# SoM.net
KiCad netlist of a schematic drawn in Altium Designer
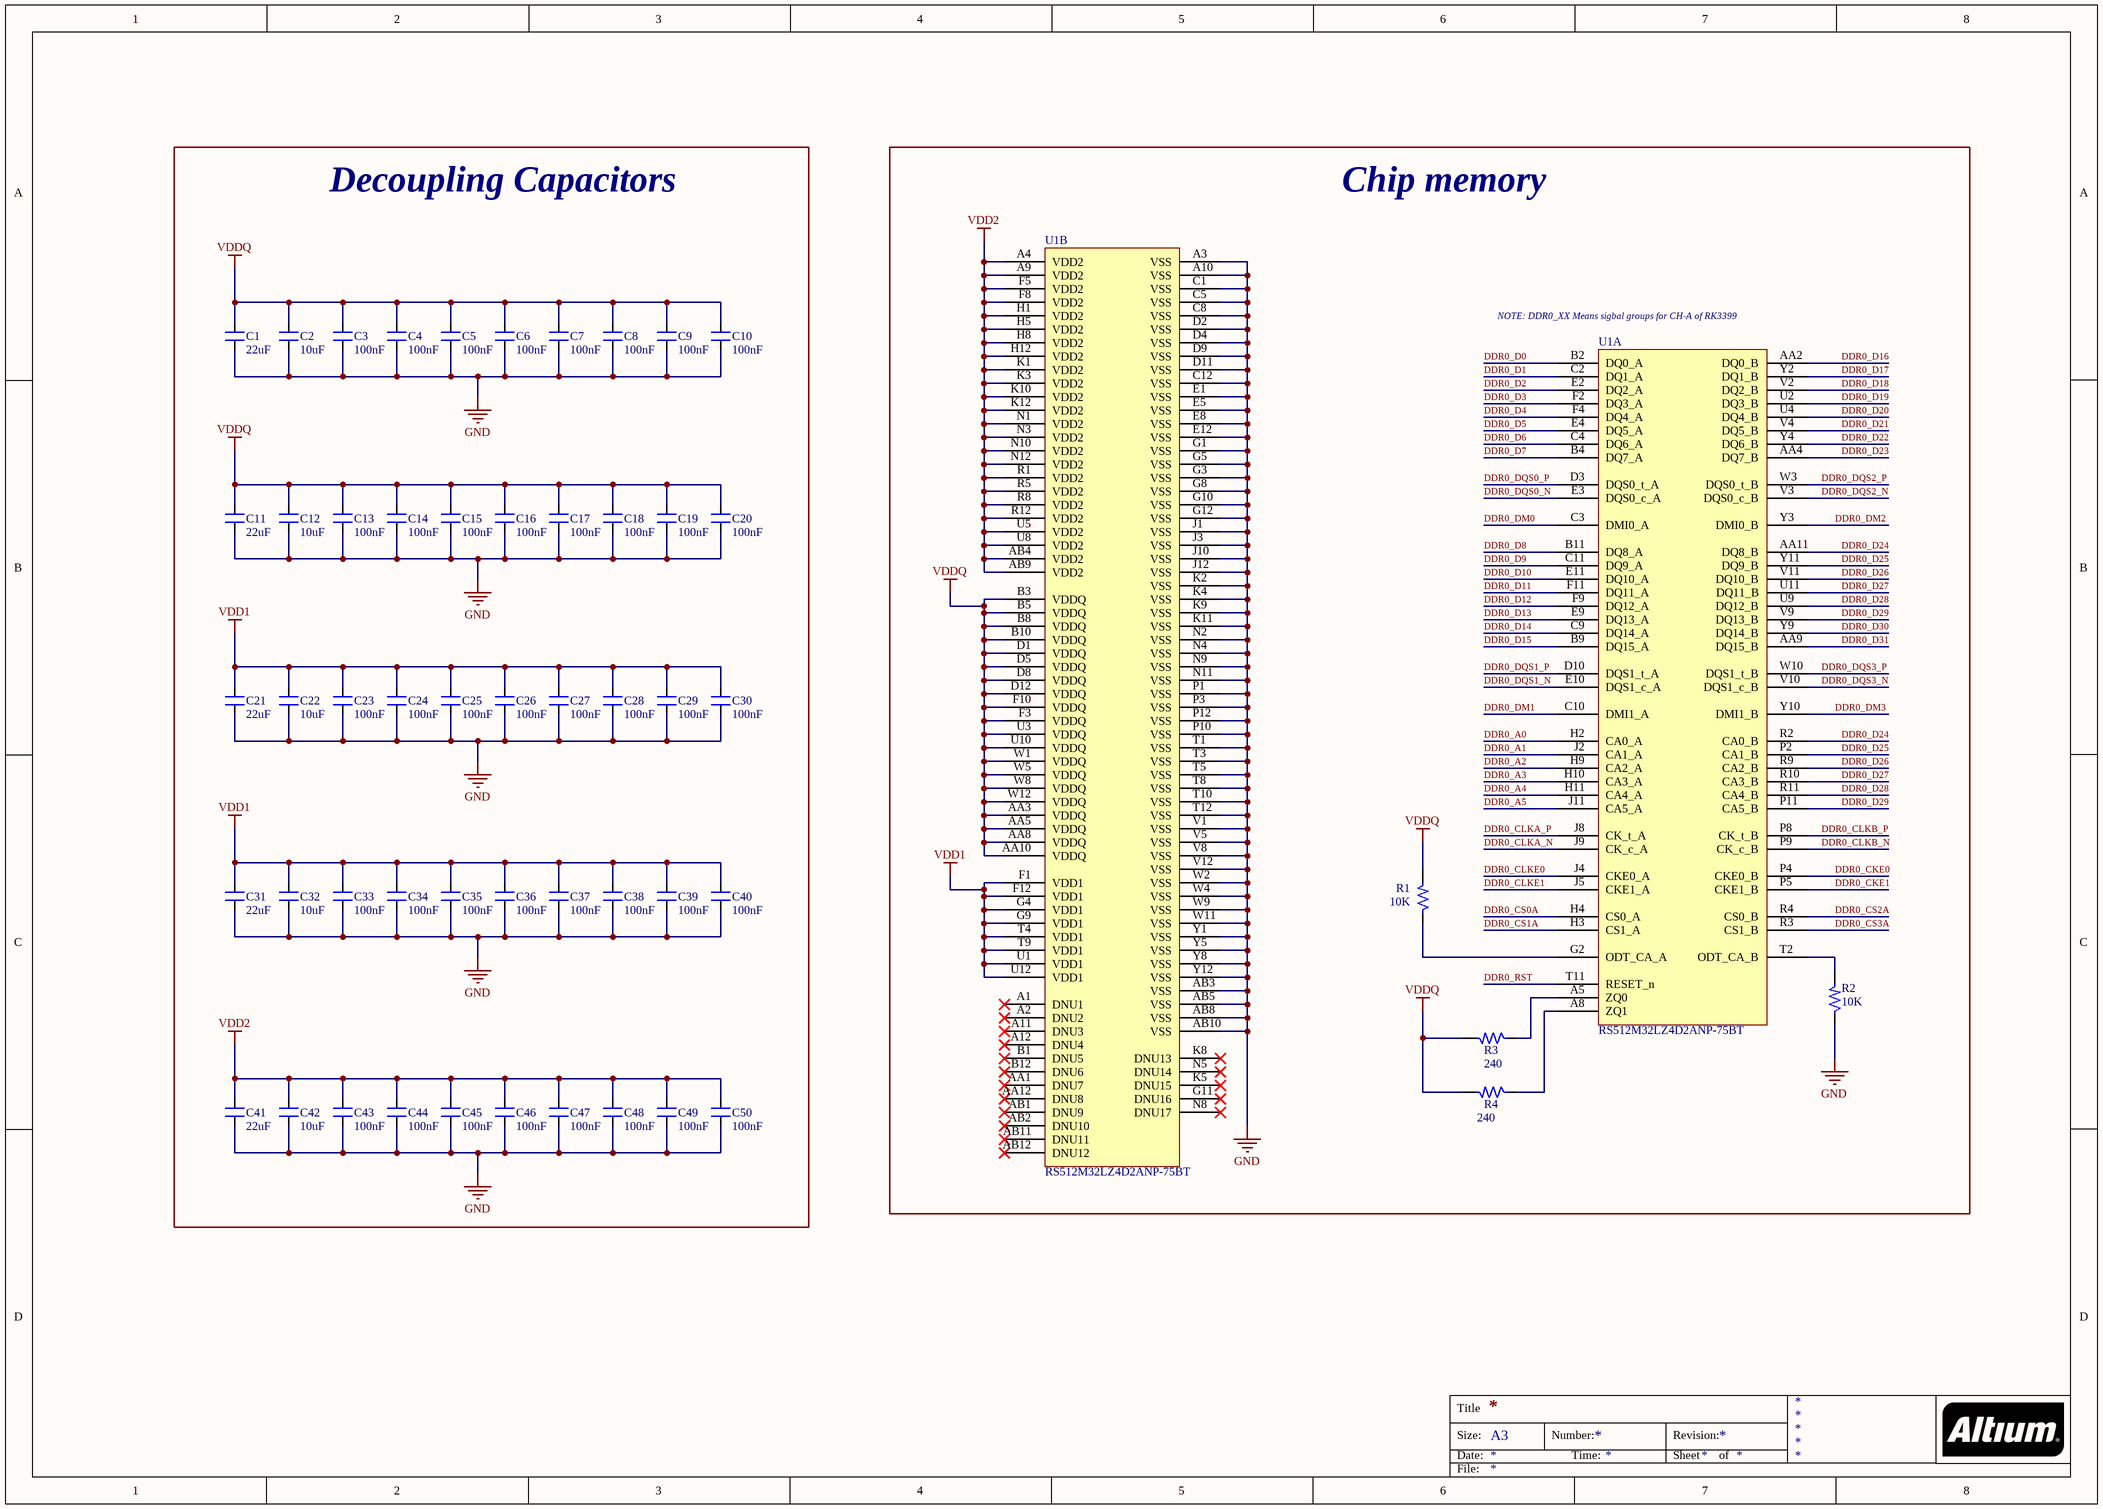
[diagram p0: SoM.SchDoc]

(export (version "E")
  (design (tool "Eeschema 10.0.6"))
  (components
    (comp (ref "C1")
      (value "22uF")
      (footprint "CAP_0603")
      (description "22µF ±20% 10V Ceramic Capacitor X5R 0603 (1608 Metric)")
      (fields
        (field (name "MANUFACTURER") "Murata Electronics")
        (field (name "MANUFACTURER PART NUMBER") "GRM188R61A226ME15D")
      )
      (libsource (lib "EsteemPCB_SOM_Course_intlib") (part "CAP_22uF-10V-20%-0603"))
    )
    (comp (ref "C2")
      (value "10uF")
      (footprint "CAP_0603")
      (description "10µF ±10% 10V Ceramic Capacitor X5R 0603 (1608 Metric)")
      (fields
        (field (name "MANUFACTURER PART NUMBER") "GRM188R61A106KE69J")
        (field (name "MANUFACTURER") "Murata Electronics")
      )
      (libsource (lib "EsteemPCB_SOM_Course_intlib") (part "CAP_10uF-10V-10%-0603"))
    )
    (comp (ref "C3")
      (value "100nF")
      (footprint "CAP_0201")
      (description "0.1µF ±10% 25V Ceramic Capacitor X5R 0201 (0603 Metric)")
      (fields
        (field (name "MANUFACTURER") "TDK Corporation")
        (field (name "MANUFACTURER PART NUMBER") "C0603X5R1E104K030BB")
      )
      (libsource (lib "EsteemPCB_SOM_Course_intlib") (part "CAP_100nF-25V-10%-0201"))
    )
    (comp (ref "C4")
      (value "100nF")
      (footprint "CAP_0201")
      (description "0.1µF ±10% 25V Ceramic Capacitor X5R 0201 (0603 Metric)")
      (fields
        (field (name "MANUFACTURER") "TDK Corporation")
        (field (name "MANUFACTURER PART NUMBER") "C0603X5R1E104K030BB")
      )
      (libsource (lib "EsteemPCB_SOM_Course_intlib") (part "CAP_100nF-25V-10%-0201"))
    )
    (comp (ref "C5")
      (value "100nF")
      (footprint "CAP_0201")
      (description "0.1µF ±10% 25V Ceramic Capacitor X5R 0201 (0603 Metric)")
      (fields
        (field (name "MANUFACTURER") "TDK Corporation")
        (field (name "MANUFACTURER PART NUMBER") "C0603X5R1E104K030BB")
      )
      (libsource (lib "EsteemPCB_SOM_Course_intlib") (part "CAP_100nF-25V-10%-0201"))
    )
    (comp (ref "C6")
      (value "100nF")
      (footprint "CAP_0201")
      (description "0.1µF ±10% 25V Ceramic Capacitor X5R 0201 (0603 Metric)")
      (fields
        (field (name "MANUFACTURER") "TDK Corporation")
        (field (name "MANUFACTURER PART NUMBER") "C0603X5R1E104K030BB")
      )
      (libsource (lib "EsteemPCB_SOM_Course_intlib") (part "CAP_100nF-25V-10%-0201"))
    )
    (comp (ref "C7")
      (value "100nF")
      (footprint "CAP_0201")
      (description "0.1µF ±10% 25V Ceramic Capacitor X5R 0201 (0603 Metric)")
      (fields
        (field (name "MANUFACTURER") "TDK Corporation")
        (field (name "MANUFACTURER PART NUMBER") "C0603X5R1E104K030BB")
      )
      (libsource (lib "EsteemPCB_SOM_Course_intlib") (part "CAP_100nF-25V-10%-0201"))
    )
    (comp (ref "C8")
      (value "100nF")
      (footprint "CAP_0201")
      (description "0.1µF ±10% 25V Ceramic Capacitor X5R 0201 (0603 Metric)")
      (fields
        (field (name "MANUFACTURER") "TDK Corporation")
        (field (name "MANUFACTURER PART NUMBER") "C0603X5R1E104K030BB")
      )
      (libsource (lib "EsteemPCB_SOM_Course_intlib") (part "CAP_100nF-25V-10%-0201"))
    )
    (comp (ref "C9")
      (value "100nF")
      (footprint "CAP_0201")
      (description "0.1µF ±10% 25V Ceramic Capacitor X5R 0201 (0603 Metric)")
      (fields
        (field (name "MANUFACTURER") "TDK Corporation")
        (field (name "MANUFACTURER PART NUMBER") "C0603X5R1E104K030BB")
      )
      (libsource (lib "EsteemPCB_SOM_Course_intlib") (part "CAP_100nF-25V-10%-0201"))
    )
    (comp (ref "C10")
      (value "100nF")
      (footprint "CAP_0201")
      (description "0.1µF ±10% 25V Ceramic Capacitor X5R 0201 (0603 Metric)")
      (fields
        (field (name "MANUFACTURER") "TDK Corporation")
        (field (name "MANUFACTURER PART NUMBER") "C0603X5R1E104K030BB")
      )
      (libsource (lib "EsteemPCB_SOM_Course_intlib") (part "CAP_100nF-25V-10%-0201"))
    )
    (comp (ref "C11")
      (value "22uF")
      (footprint "CAP_0603")
      (description "22µF ±20% 10V Ceramic Capacitor X5R 0603 (1608 Metric)")
      (fields
        (field (name "MANUFACTURER") "Murata Electronics")
        (field (name "MANUFACTURER PART NUMBER") "GRM188R61A226ME15D")
      )
      (libsource (lib "EsteemPCB_SOM_Course_intlib") (part "CAP_22uF-10V-20%-0603"))
    )
    (comp (ref "C12")
      (value "10uF")
      (footprint "CAP_0603")
      (description "10µF ±10% 10V Ceramic Capacitor X5R 0603 (1608 Metric)")
      (fields
        (field (name "MANUFACTURER PART NUMBER") "GRM188R61A106KE69J")
        (field (name "MANUFACTURER") "Murata Electronics")
      )
      (libsource (lib "EsteemPCB_SOM_Course_intlib") (part "CAP_10uF-10V-10%-0603"))
    )
    (comp (ref "C13")
      (value "100nF")
      (footprint "CAP_0201")
      (description "0.1µF ±10% 25V Ceramic Capacitor X5R 0201 (0603 Metric)")
      (fields
        (field (name "MANUFACTURER") "TDK Corporation")
        (field (name "MANUFACTURER PART NUMBER") "C0603X5R1E104K030BB")
      )
      (libsource (lib "EsteemPCB_SOM_Course_intlib") (part "CAP_100nF-25V-10%-0201"))
    )
    (comp (ref "C14")
      (value "100nF")
      (footprint "CAP_0201")
      (description "0.1µF ±10% 25V Ceramic Capacitor X5R 0201 (0603 Metric)")
      (fields
        (field (name "MANUFACTURER") "TDK Corporation")
        (field (name "MANUFACTURER PART NUMBER") "C0603X5R1E104K030BB")
      )
      (libsource (lib "EsteemPCB_SOM_Course_intlib") (part "CAP_100nF-25V-10%-0201"))
    )
    (comp (ref "C15")
      (value "100nF")
      (footprint "CAP_0201")
      (description "0.1µF ±10% 25V Ceramic Capacitor X5R 0201 (0603 Metric)")
      (fields
        (field (name "MANUFACTURER") "TDK Corporation")
        (field (name "MANUFACTURER PART NUMBER") "C0603X5R1E104K030BB")
      )
      (libsource (lib "EsteemPCB_SOM_Course_intlib") (part "CAP_100nF-25V-10%-0201"))
    )
    (comp (ref "C16")
      (value "100nF")
      (footprint "CAP_0201")
      (description "0.1µF ±10% 25V Ceramic Capacitor X5R 0201 (0603 Metric)")
      (fields
        (field (name "MANUFACTURER") "TDK Corporation")
        (field (name "MANUFACTURER PART NUMBER") "C0603X5R1E104K030BB")
      )
      (libsource (lib "EsteemPCB_SOM_Course_intlib") (part "CAP_100nF-25V-10%-0201"))
    )
    (comp (ref "C17")
      (value "100nF")
      (footprint "CAP_0201")
      (description "0.1µF ±10% 25V Ceramic Capacitor X5R 0201 (0603 Metric)")
      (fields
        (field (name "MANUFACTURER") "TDK Corporation")
        (field (name "MANUFACTURER PART NUMBER") "C0603X5R1E104K030BB")
      )
      (libsource (lib "EsteemPCB_SOM_Course_intlib") (part "CAP_100nF-25V-10%-0201"))
    )
    (comp (ref "C18")
      (value "100nF")
      (footprint "CAP_0201")
      (description "0.1µF ±10% 25V Ceramic Capacitor X5R 0201 (0603 Metric)")
      (fields
        (field (name "MANUFACTURER") "TDK Corporation")
        (field (name "MANUFACTURER PART NUMBER") "C0603X5R1E104K030BB")
      )
      (libsource (lib "EsteemPCB_SOM_Course_intlib") (part "CAP_100nF-25V-10%-0201"))
    )
    (comp (ref "C19")
      (value "100nF")
      (footprint "CAP_0201")
      (description "0.1µF ±10% 25V Ceramic Capacitor X5R 0201 (0603 Metric)")
      (fields
        (field (name "MANUFACTURER") "TDK Corporation")
        (field (name "MANUFACTURER PART NUMBER") "C0603X5R1E104K030BB")
      )
      (libsource (lib "EsteemPCB_SOM_Course_intlib") (part "CAP_100nF-25V-10%-0201"))
    )
    (comp (ref "C20")
      (value "100nF")
      (footprint "CAP_0201")
      (description "0.1µF ±10% 25V Ceramic Capacitor X5R 0201 (0603 Metric)")
      (fields
        (field (name "MANUFACTURER") "TDK Corporation")
        (field (name "MANUFACTURER PART NUMBER") "C0603X5R1E104K030BB")
      )
      (libsource (lib "EsteemPCB_SOM_Course_intlib") (part "CAP_100nF-25V-10%-0201"))
    )
    (comp (ref "C21")
      (value "22uF")
      (footprint "CAP_0603")
      (description "22µF ±20% 10V Ceramic Capacitor X5R 0603 (1608 Metric)")
      (fields
        (field (name "MANUFACTURER") "Murata Electronics")
        (field (name "MANUFACTURER PART NUMBER") "GRM188R61A226ME15D")
      )
      (libsource (lib "EsteemPCB_SOM_Course_intlib") (part "CAP_22uF-10V-20%-0603"))
    )
    (comp (ref "C22")
      (value "10uF")
      (footprint "CAP_0603")
      (description "10µF ±10% 10V Ceramic Capacitor X5R 0603 (1608 Metric)")
      (fields
        (field (name "MANUFACTURER PART NUMBER") "GRM188R61A106KE69J")
        (field (name "MANUFACTURER") "Murata Electronics")
      )
      (libsource (lib "EsteemPCB_SOM_Course_intlib") (part "CAP_10uF-10V-10%-0603"))
    )
    (comp (ref "C23")
      (value "100nF")
      (footprint "CAP_0201")
      (description "0.1µF ±10% 25V Ceramic Capacitor X5R 0201 (0603 Metric)")
      (fields
        (field (name "MANUFACTURER") "TDK Corporation")
        (field (name "MANUFACTURER PART NUMBER") "C0603X5R1E104K030BB")
      )
      (libsource (lib "EsteemPCB_SOM_Course_intlib") (part "CAP_100nF-25V-10%-0201"))
    )
    (comp (ref "C24")
      (value "100nF")
      (footprint "CAP_0201")
      (description "0.1µF ±10% 25V Ceramic Capacitor X5R 0201 (0603 Metric)")
      (fields
        (field (name "MANUFACTURER") "TDK Corporation")
        (field (name "MANUFACTURER PART NUMBER") "C0603X5R1E104K030BB")
      )
      (libsource (lib "EsteemPCB_SOM_Course_intlib") (part "CAP_100nF-25V-10%-0201"))
    )
    (comp (ref "C25")
      (value "100nF")
      (footprint "CAP_0201")
      (description "0.1µF ±10% 25V Ceramic Capacitor X5R 0201 (0603 Metric)")
      (fields
        (field (name "MANUFACTURER") "TDK Corporation")
        (field (name "MANUFACTURER PART NUMBER") "C0603X5R1E104K030BB")
      )
      (libsource (lib "EsteemPCB_SOM_Course_intlib") (part "CAP_100nF-25V-10%-0201"))
    )
    (comp (ref "C26")
      (value "100nF")
      (footprint "CAP_0201")
      (description "0.1µF ±10% 25V Ceramic Capacitor X5R 0201 (0603 Metric)")
      (fields
        (field (name "MANUFACTURER") "TDK Corporation")
        (field (name "MANUFACTURER PART NUMBER") "C0603X5R1E104K030BB")
      )
      (libsource (lib "EsteemPCB_SOM_Course_intlib") (part "CAP_100nF-25V-10%-0201"))
    )
    (comp (ref "C27")
      (value "100nF")
      (footprint "CAP_0201")
      (description "0.1µF ±10% 25V Ceramic Capacitor X5R 0201 (0603 Metric)")
      (fields
        (field (name "MANUFACTURER") "TDK Corporation")
        (field (name "MANUFACTURER PART NUMBER") "C0603X5R1E104K030BB")
      )
      (libsource (lib "EsteemPCB_SOM_Course_intlib") (part "CAP_100nF-25V-10%-0201"))
    )
    (comp (ref "C28")
      (value "100nF")
      (footprint "CAP_0201")
      (description "0.1µF ±10% 25V Ceramic Capacitor X5R 0201 (0603 Metric)")
      (fields
        (field (name "MANUFACTURER") "TDK Corporation")
        (field (name "MANUFACTURER PART NUMBER") "C0603X5R1E104K030BB")
      )
      (libsource (lib "EsteemPCB_SOM_Course_intlib") (part "CAP_100nF-25V-10%-0201"))
    )
    (comp (ref "C29")
      (value "100nF")
      (footprint "CAP_0201")
      (description "0.1µF ±10% 25V Ceramic Capacitor X5R 0201 (0603 Metric)")
      (fields
        (field (name "MANUFACTURER") "TDK Corporation")
        (field (name "MANUFACTURER PART NUMBER") "C0603X5R1E104K030BB")
      )
      (libsource (lib "EsteemPCB_SOM_Course_intlib") (part "CAP_100nF-25V-10%-0201"))
    )
    (comp (ref "C30")
      (value "100nF")
      (footprint "CAP_0201")
      (description "0.1µF ±10% 25V Ceramic Capacitor X5R 0201 (0603 Metric)")
      (fields
        (field (name "MANUFACTURER") "TDK Corporation")
        (field (name "MANUFACTURER PART NUMBER") "C0603X5R1E104K030BB")
      )
      (libsource (lib "EsteemPCB_SOM_Course_intlib") (part "CAP_100nF-25V-10%-0201"))
    )
    (comp (ref "C31")
      (value "22uF")
      (footprint "CAP_0603")
      (description "22µF ±20% 10V Ceramic Capacitor X5R 0603 (1608 Metric)")
      (fields
        (field (name "MANUFACTURER") "Murata Electronics")
        (field (name "MANUFACTURER PART NUMBER") "GRM188R61A226ME15D")
      )
      (libsource (lib "EsteemPCB_SOM_Course_intlib") (part "CAP_22uF-10V-20%-0603"))
    )
    (comp (ref "C32")
      (value "10uF")
      (footprint "CAP_0603")
      (description "10µF ±10% 10V Ceramic Capacitor X5R 0603 (1608 Metric)")
      (fields
        (field (name "MANUFACTURER PART NUMBER") "GRM188R61A106KE69J")
        (field (name "MANUFACTURER") "Murata Electronics")
      )
      (libsource (lib "EsteemPCB_SOM_Course_intlib") (part "CAP_10uF-10V-10%-0603"))
    )
    (comp (ref "C33")
      (value "100nF")
      (footprint "CAP_0201")
      (description "0.1µF ±10% 25V Ceramic Capacitor X5R 0201 (0603 Metric)")
      (fields
        (field (name "MANUFACTURER") "TDK Corporation")
        (field (name "MANUFACTURER PART NUMBER") "C0603X5R1E104K030BB")
      )
      (libsource (lib "EsteemPCB_SOM_Course_intlib") (part "CAP_100nF-25V-10%-0201"))
    )
    (comp (ref "C34")
      (value "100nF")
      (footprint "CAP_0201")
      (description "0.1µF ±10% 25V Ceramic Capacitor X5R 0201 (0603 Metric)")
      (fields
        (field (name "MANUFACTURER") "TDK Corporation")
        (field (name "MANUFACTURER PART NUMBER") "C0603X5R1E104K030BB")
      )
      (libsource (lib "EsteemPCB_SOM_Course_intlib") (part "CAP_100nF-25V-10%-0201"))
    )
    (comp (ref "C35")
      (value "100nF")
      (footprint "CAP_0201")
      (description "0.1µF ±10% 25V Ceramic Capacitor X5R 0201 (0603 Metric)")
      (fields
        (field (name "MANUFACTURER") "TDK Corporation")
        (field (name "MANUFACTURER PART NUMBER") "C0603X5R1E104K030BB")
      )
      (libsource (lib "EsteemPCB_SOM_Course_intlib") (part "CAP_100nF-25V-10%-0201"))
    )
    (comp (ref "C36")
      (value "100nF")
      (footprint "CAP_0201")
      (description "0.1µF ±10% 25V Ceramic Capacitor X5R 0201 (0603 Metric)")
      (fields
        (field (name "MANUFACTURER") "TDK Corporation")
        (field (name "MANUFACTURER PART NUMBER") "C0603X5R1E104K030BB")
      )
      (libsource (lib "EsteemPCB_SOM_Course_intlib") (part "CAP_100nF-25V-10%-0201"))
    )
    (comp (ref "C37")
      (value "100nF")
      (footprint "CAP_0201")
      (description "0.1µF ±10% 25V Ceramic Capacitor X5R 0201 (0603 Metric)")
      (fields
        (field (name "MANUFACTURER") "TDK Corporation")
        (field (name "MANUFACTURER PART NUMBER") "C0603X5R1E104K030BB")
      )
      (libsource (lib "EsteemPCB_SOM_Course_intlib") (part "CAP_100nF-25V-10%-0201"))
    )
    (comp (ref "C38")
      (value "100nF")
      (footprint "CAP_0201")
      (description "0.1µF ±10% 25V Ceramic Capacitor X5R 0201 (0603 Metric)")
      (fields
        (field (name "MANUFACTURER") "TDK Corporation")
        (field (name "MANUFACTURER PART NUMBER") "C0603X5R1E104K030BB")
      )
      (libsource (lib "EsteemPCB_SOM_Course_intlib") (part "CAP_100nF-25V-10%-0201"))
    )
    (comp (ref "C39")
      (value "100nF")
      (footprint "CAP_0201")
      (description "0.1µF ±10% 25V Ceramic Capacitor X5R 0201 (0603 Metric)")
      (fields
        (field (name "MANUFACTURER") "TDK Corporation")
        (field (name "MANUFACTURER PART NUMBER") "C0603X5R1E104K030BB")
      )
      (libsource (lib "EsteemPCB_SOM_Course_intlib") (part "CAP_100nF-25V-10%-0201"))
    )
    (comp (ref "C40")
      (value "100nF")
      (footprint "CAP_0201")
      (description "0.1µF ±10% 25V Ceramic Capacitor X5R 0201 (0603 Metric)")
      (fields
        (field (name "MANUFACTURER") "TDK Corporation")
        (field (name "MANUFACTURER PART NUMBER") "C0603X5R1E104K030BB")
      )
      (libsource (lib "EsteemPCB_SOM_Course_intlib") (part "CAP_100nF-25V-10%-0201"))
    )
    (comp (ref "C41")
      (value "22uF")
      (footprint "CAP_0603")
      (description "22µF ±20% 10V Ceramic Capacitor X5R 0603 (1608 Metric)")
      (fields
        (field (name "MANUFACTURER") "Murata Electronics")
        (field (name "MANUFACTURER PART NUMBER") "GRM188R61A226ME15D")
      )
      (libsource (lib "EsteemPCB_SOM_Course_intlib") (part "CAP_22uF-10V-20%-0603"))
    )
    (comp (ref "C42")
      (value "10uF")
      (footprint "CAP_0603")
      (description "10µF ±10% 10V Ceramic Capacitor X5R 0603 (1608 Metric)")
      (fields
        (field (name "MANUFACTURER PART NUMBER") "GRM188R61A106KE69J")
        (field (name "MANUFACTURER") "Murata Electronics")
      )
      (libsource (lib "EsteemPCB_SOM_Course_intlib") (part "CAP_10uF-10V-10%-0603"))
    )
    (comp (ref "C43")
      (value "100nF")
      (footprint "CAP_0201")
      (description "0.1µF ±10% 25V Ceramic Capacitor X5R 0201 (0603 Metric)")
      (fields
        (field (name "MANUFACTURER") "TDK Corporation")
        (field (name "MANUFACTURER PART NUMBER") "C0603X5R1E104K030BB")
      )
      (libsource (lib "EsteemPCB_SOM_Course_intlib") (part "CAP_100nF-25V-10%-0201"))
    )
    (comp (ref "C44")
      (value "100nF")
      (footprint "CAP_0201")
      (description "0.1µF ±10% 25V Ceramic Capacitor X5R 0201 (0603 Metric)")
      (fields
        (field (name "MANUFACTURER") "TDK Corporation")
        (field (name "MANUFACTURER PART NUMBER") "C0603X5R1E104K030BB")
      )
      (libsource (lib "EsteemPCB_SOM_Course_intlib") (part "CAP_100nF-25V-10%-0201"))
    )
    (comp (ref "C45")
      (value "100nF")
      (footprint "CAP_0201")
      (description "0.1µF ±10% 25V Ceramic Capacitor X5R 0201 (0603 Metric)")
      (fields
        (field (name "MANUFACTURER") "TDK Corporation")
        (field (name "MANUFACTURER PART NUMBER") "C0603X5R1E104K030BB")
      )
      (libsource (lib "EsteemPCB_SOM_Course_intlib") (part "CAP_100nF-25V-10%-0201"))
    )
    (comp (ref "C46")
      (value "100nF")
      (footprint "CAP_0201")
      (description "0.1µF ±10% 25V Ceramic Capacitor X5R 0201 (0603 Metric)")
      (fields
        (field (name "MANUFACTURER") "TDK Corporation")
        (field (name "MANUFACTURER PART NUMBER") "C0603X5R1E104K030BB")
      )
      (libsource (lib "EsteemPCB_SOM_Course_intlib") (part "CAP_100nF-25V-10%-0201"))
    )
    (comp (ref "C47")
      (value "100nF")
      (footprint "CAP_0201")
      (description "0.1µF ±10% 25V Ceramic Capacitor X5R 0201 (0603 Metric)")
      (fields
        (field (name "MANUFACTURER") "TDK Corporation")
        (field (name "MANUFACTURER PART NUMBER") "C0603X5R1E104K030BB")
      )
      (libsource (lib "EsteemPCB_SOM_Course_intlib") (part "CAP_100nF-25V-10%-0201"))
    )
    (comp (ref "C48")
      (value "100nF")
      (footprint "CAP_0201")
      (description "0.1µF ±10% 25V Ceramic Capacitor X5R 0201 (0603 Metric)")
      (fields
        (field (name "MANUFACTURER") "TDK Corporation")
        (field (name "MANUFACTURER PART NUMBER") "C0603X5R1E104K030BB")
      )
      (libsource (lib "EsteemPCB_SOM_Course_intlib") (part "CAP_100nF-25V-10%-0201"))
    )
    (comp (ref "C49")
      (value "100nF")
      (footprint "CAP_0201")
      (description "0.1µF ±10% 25V Ceramic Capacitor X5R 0201 (0603 Metric)")
      (fields
        (field (name "MANUFACTURER") "TDK Corporation")
        (field (name "MANUFACTURER PART NUMBER") "C0603X5R1E104K030BB")
      )
      (libsource (lib "EsteemPCB_SOM_Course_intlib") (part "CAP_100nF-25V-10%-0201"))
    )
    (comp (ref "C50")
      (value "100nF")
      (footprint "CAP_0201")
      (description "0.1µF ±10% 25V Ceramic Capacitor X5R 0201 (0603 Metric)")
      (fields
        (field (name "MANUFACTURER") "TDK Corporation")
        (field (name "MANUFACTURER PART NUMBER") "C0603X5R1E104K030BB")
      )
      (libsource (lib "EsteemPCB_SOM_Course_intlib") (part "CAP_100nF-25V-10%-0201"))
    )
    (comp (ref "R1")
      (value "10K")
      (footprint "RES_0201")
      (description "10 kOhms ±1% 0.05W, 1/20W Chip Resistor 0201 (0603 Metric) Thick Film")
      (fields
        (field (name "MANUFACTURER") "Stackpole Electronics Inc")
        (field (name "MANUFACTURER PART NUMBER") "RMCF0201FT10K0")
      )
      (libsource (lib "EsteemPCB_SOM_Course_intlib") (part "RES_10K-0.05W-1%-0201"))
    )
    (comp (ref "R2")
      (value "10K")
      (footprint "RES_0201")
      (description "10 kOhms ±1% 0.05W, 1/20W Chip Resistor 0201 (0603 Metric) Thick Film")
      (fields
        (field (name "MANUFACTURER") "Stackpole Electronics Inc")
        (field (name "MANUFACTURER PART NUMBER") "RMCF0201FT10K0")
      )
      (libsource (lib "EsteemPCB_SOM_Course_intlib") (part "RES_10K-0.05W-1%-0201"))
    )
    (comp (ref "R3")
      (value "240")
      (footprint "RES_0201")
      (description "10 kOhms ±1% 0.05W, 1/20W Chip Resistor 0201 (0603 Metric) Thick Film")
      (fields
        (field (name "MANUFACTURER") "Stackpole Electronics Inc")
        (field (name "MANUFACTURER PART NUMBER") "RMCF0201FT10K0")
      )
      (libsource (lib "EsteemPCB_SOM_Course_intlib") (part "RES_10K-0.05W-1%-0201"))
    )
    (comp (ref "R4")
      (value "240")
      (footprint "RES_0201")
      (description "10 kOhms ±1% 0.05W, 1/20W Chip Resistor 0201 (0603 Metric) Thick Film")
      (fields
        (field (name "MANUFACTURER") "Stackpole Electronics Inc")
        (field (name "MANUFACTURER PART NUMBER") "RMCF0201FT10K0")
      )
      (libsource (lib "EsteemPCB_SOM_Course_intlib") (part "RES_10K-0.05W-1%-0201"))
    )
    (comp (ref "U1")
      (value "RS512M32LZ4D2ANP-75BT")
      (footprint "FBGA200_SMD")
      (fields (field (name "MANUFACTURER") "RAYSON"))
      (libsource (lib "EsteemPCB_SOM_Course_intlib") (part "IC_RS512M32LZ4D2ANP-75BT"))
    )
  )
  (nets
    (net (code "1") (name "/DDR0_A0") (class "Default")
      (node (ref "U1") (pin "H2") (pinfunction "CA0_A_H2") (pintype "passive"))
    )
    (net (code "2") (name "/DDR0_A1") (class "Default")
      (node (ref "U1") (pin "J2") (pinfunction "CA1_A_J2") (pintype "passive"))
    )
    (net (code "3") (name "/DDR0_A2") (class "Default")
      (node (ref "U1") (pin "H9") (pinfunction "CA2_A_H9") (pintype "passive"))
    )
    (net (code "4") (name "/DDR0_A3") (class "Default")
      (node (ref "U1") (pin "H10") (pinfunction "CA3_A_H10") (pintype "passive"))
    )
    (net (code "5") (name "/DDR0_A4") (class "Default")
      (node (ref "U1") (pin "H11") (pinfunction "CA4_A_H11") (pintype "passive"))
    )
    (net (code "6") (name "/DDR0_A5") (class "Default")
      (node (ref "U1") (pin "J11") (pinfunction "CA5_A_J11") (pintype "passive"))
    )
    (net (code "7") (name "/DDR0_CKE0") (class "Default")
      (node (ref "U1") (pin "P4") (pinfunction "CKE0_B_P4") (pintype "passive"))
    )
    (net (code "8") (name "/DDR0_CKE1") (class "Default")
      (node (ref "U1") (pin "P5") (pinfunction "CKE1_B_P5") (pintype "passive"))
    )
    (net (code "9") (name "/DDR0_CLKA_N") (class "Default")
      (node (ref "U1") (pin "J9") (pinfunction "CK_c_A_J9") (pintype "passive"))
    )
    (net (code "10") (name "/DDR0_CLKA_P") (class "Default")
      (node (ref "U1") (pin "J8") (pinfunction "CK_t_A_J8") (pintype "passive"))
    )
    (net (code "11") (name "/DDR0_CLKB_N") (class "Default")
      (node (ref "U1") (pin "P9") (pinfunction "CK_c_B_P9") (pintype "passive"))
    )
    (net (code "12") (name "/DDR0_CLKB_P") (class "Default")
      (node (ref "U1") (pin "P8") (pinfunction "CK_t_B_P8") (pintype "passive"))
    )
    (net (code "13") (name "/DDR0_CLKE0") (class "Default")
      (node (ref "U1") (pin "J4") (pinfunction "CKE0_A_J4") (pintype "passive"))
    )
    (net (code "14") (name "/DDR0_CLKE1") (class "Default")
      (node (ref "U1") (pin "J5") (pinfunction "CKE1_A_J5") (pintype "passive"))
    )
    (net (code "15") (name "/DDR0_CS0A") (class "Default")
      (node (ref "U1") (pin "H4") (pinfunction "CS0_A_H4") (pintype "passive"))
    )
    (net (code "16") (name "/DDR0_CS1A") (class "Default")
      (node (ref "U1") (pin "H3") (pinfunction "CS1_A_H3") (pintype "passive"))
    )
    (net (code "17") (name "/DDR0_CS2A") (class "Default")
      (node (ref "U1") (pin "R4") (pinfunction "CS0_B_R4") (pintype "passive"))
    )
    (net (code "18") (name "/DDR0_CS3A") (class "Default")
      (node (ref "U1") (pin "R3") (pinfunction "CS1_B_R3") (pintype "passive"))
    )
    (net (code "19") (name "/DDR0_D0") (class "Default")
      (node (ref "U1") (pin "B2") (pinfunction "DQ0_A_B2") (pintype "passive"))
    )
    (net (code "20") (name "/DDR0_D1") (class "Default")
      (node (ref "U1") (pin "C2") (pinfunction "DQ1_A_C2") (pintype "passive"))
    )
    (net (code "21") (name "/DDR0_D2") (class "Default")
      (node (ref "U1") (pin "E2") (pinfunction "DQ2_A_E2") (pintype "passive"))
    )
    (net (code "22") (name "/DDR0_D3") (class "Default")
      (node (ref "U1") (pin "F2") (pinfunction "DQ3_A_F2") (pintype "passive"))
    )
    (net (code "23") (name "/DDR0_D4") (class "Default")
      (node (ref "U1") (pin "F4") (pinfunction "DQ4_A_F4") (pintype "passive"))
    )
    (net (code "24") (name "/DDR0_D5") (class "Default")
      (node (ref "U1") (pin "E4") (pinfunction "DQ5_A_E4") (pintype "passive"))
    )
    (net (code "25") (name "/DDR0_D6") (class "Default")
      (node (ref "U1") (pin "C4") (pinfunction "DQ6_A_C4") (pintype "passive"))
    )
    (net (code "26") (name "/DDR0_D7") (class "Default")
      (node (ref "U1") (pin "B4") (pinfunction "DQ7_A_B4") (pintype "passive"))
    )
    (net (code "27") (name "/DDR0_D8") (class "Default")
      (node (ref "U1") (pin "B11") (pinfunction "DQ8_A_B11") (pintype "passive"))
    )
    (net (code "28") (name "/DDR0_D9") (class "Default")
      (node (ref "U1") (pin "C11") (pinfunction "DQ9_A_C11") (pintype "passive"))
    )
    (net (code "29") (name "/DDR0_D10") (class "Default")
      (node (ref "U1") (pin "E11") (pinfunction "DQ10_A_E11") (pintype "passive"))
    )
    (net (code "30") (name "/DDR0_D11") (class "Default")
      (node (ref "U1") (pin "F11") (pinfunction "DQ11_A_F11") (pintype "passive"))
    )
    (net (code "31") (name "/DDR0_D12") (class "Default")
      (node (ref "U1") (pin "F9") (pinfunction "DQ12_A_F9") (pintype "passive"))
    )
    (net (code "32") (name "/DDR0_D13") (class "Default")
      (node (ref "U1") (pin "E9") (pinfunction "DQ13_A_E9") (pintype "passive"))
    )
    (net (code "33") (name "/DDR0_D14") (class "Default")
      (node (ref "U1") (pin "C9") (pinfunction "DQ14_A_C9") (pintype "passive"))
    )
    (net (code "34") (name "/DDR0_D15") (class "Default")
      (node (ref "U1") (pin "B9") (pinfunction "DQ15_A_B9") (pintype "passive"))
    )
    (net (code "35") (name "/DDR0_D16") (class "Default")
      (node (ref "U1") (pin "AA2") (pinfunction "DQ0_B_AA2") (pintype "passive"))
    )
    (net (code "36") (name "/DDR0_D17") (class "Default")
      (node (ref "U1") (pin "Y2") (pinfunction "DQ1_B_Y2") (pintype "passive"))
    )
    (net (code "37") (name "/DDR0_D18") (class "Default")
      (node (ref "U1") (pin "V2") (pinfunction "DQ2_B_V2") (pintype "passive"))
    )
    (net (code "38") (name "/DDR0_D19") (class "Default")
      (node (ref "U1") (pin "U2") (pinfunction "DQ3_B_U2") (pintype "passive"))
    )
    (net (code "39") (name "/DDR0_D20") (class "Default")
      (node (ref "U1") (pin "U4") (pinfunction "DQ4_B_U4") (pintype "passive"))
    )
    (net (code "40") (name "/DDR0_D21") (class "Default")
      (node (ref "U1") (pin "V4") (pinfunction "DQ5_B_V4") (pintype "passive"))
    )
    (net (code "41") (name "/DDR0_D22") (class "Default")
      (node (ref "U1") (pin "Y4") (pinfunction "DQ6_B_Y4") (pintype "passive"))
    )
    (net (code "42") (name "/DDR0_D23") (class "Default")
      (node (ref "U1") (pin "AA4") (pinfunction "DQ7_B_AA4") (pintype "passive"))
    )
    (net (code "43") (name "/DDR0_D24") (class "Default")
      (node (ref "U1") (pin "AA11") (pinfunction "DQ8_B_AA11") (pintype "passive"))
      (node (ref "U1") (pin "R2") (pinfunction "CA0_B_R2") (pintype "passive"))
    )
    (net (code "44") (name "/DDR0_D25") (class "Default")
      (node (ref "U1") (pin "P2") (pinfunction "CA1_B_P2") (pintype "passive"))
      (node (ref "U1") (pin "Y11") (pinfunction "DQ9_B_Y11") (pintype "passive"))
    )
    (net (code "45") (name "/DDR0_D26") (class "Default")
      (node (ref "U1") (pin "R9") (pinfunction "CA2_B_R9") (pintype "passive"))
      (node (ref "U1") (pin "V11") (pinfunction "DQ10_B_V11") (pintype "passive"))
    )
    (net (code "46") (name "/DDR0_D27") (class "Default")
      (node (ref "U1") (pin "R10") (pinfunction "CA3_B_R10") (pintype "passive"))
      (node (ref "U1") (pin "U11") (pinfunction "DQ11_B_U11") (pintype "passive"))
    )
    (net (code "47") (name "/DDR0_D28") (class "Default")
      (node (ref "U1") (pin "R11") (pinfunction "CA4_B_R11") (pintype "passive"))
      (node (ref "U1") (pin "U9") (pinfunction "DQ12_B_U9") (pintype "passive"))
    )
    (net (code "48") (name "/DDR0_D29") (class "Default")
      (node (ref "U1") (pin "P11") (pinfunction "CA5_B_P11") (pintype "passive"))
      (node (ref "U1") (pin "V9") (pinfunction "DQ13_B_V9") (pintype "passive"))
    )
    (net (code "49") (name "/DDR0_D30") (class "Default")
      (node (ref "U1") (pin "Y9") (pinfunction "DQ14_B_Y9") (pintype "passive"))
    )
    (net (code "50") (name "/DDR0_D31") (class "Default")
      (node (ref "U1") (pin "AA9") (pinfunction "DQ15_B_AA9") (pintype "passive"))
    )
    (net (code "51") (name "/DDR0_DM0") (class "Default")
      (node (ref "U1") (pin "C3") (pinfunction "DMI0_A_C3") (pintype "passive"))
    )
    (net (code "52") (name "/DDR0_DM1") (class "Default")
      (node (ref "U1") (pin "C10") (pinfunction "DMI1_A_C10") (pintype "passive"))
    )
    (net (code "53") (name "/DDR0_DM2") (class "Default")
      (node (ref "U1") (pin "Y3") (pinfunction "DMI0_B_Y3") (pintype "passive"))
    )
    (net (code "54") (name "/DDR0_DM3") (class "Default")
      (node (ref "U1") (pin "Y10") (pinfunction "DMI1_B_Y10") (pintype "passive"))
    )
    (net (code "55") (name "/DDR0_DQS0_N") (class "Default")
      (node (ref "U1") (pin "E3") (pinfunction "DQS0_c_A_E3") (pintype "passive"))
    )
    (net (code "56") (name "/DDR0_DQS0_P") (class "Default")
      (node (ref "U1") (pin "D3") (pinfunction "DQS0_t_A_D3") (pintype "passive"))
    )
    (net (code "57") (name "/DDR0_DQS1_N") (class "Default")
      (node (ref "U1") (pin "E10") (pinfunction "DQS1_c_A_E10") (pintype "passive"))
    )
    (net (code "58") (name "/DDR0_DQS1_P") (class "Default")
      (node (ref "U1") (pin "D10") (pinfunction "DQS1_t_A_D10") (pintype "passive"))
    )
    (net (code "59") (name "/DDR0_DQS2_N") (class "Default")
      (node (ref "U1") (pin "V3") (pinfunction "DQS0_c_B_V3") (pintype "passive"))
    )
    (net (code "60") (name "/DDR0_DQS2_P") (class "Default")
      (node (ref "U1") (pin "W3") (pinfunction "DQS0_t_B_W3") (pintype "passive"))
    )
    (net (code "61") (name "/DDR0_DQS3_N") (class "Default")
      (node (ref "U1") (pin "V10") (pinfunction "DQS1_c_B_V10") (pintype "passive"))
    )
    (net (code "62") (name "/DDR0_DQS3_P") (class "Default")
      (node (ref "U1") (pin "W10") (pinfunction "DQS1_t_B_W10") (pintype "passive"))
    )
    (net (code "63") (name "/DDR0_RST") (class "Default")
      (node (ref "U1") (pin "T11") (pinfunction "RESET_n_T11") (pintype "passive"))
    )
    (net (code "64") (name "GND") (class "Default")
      (node (ref "C1") (pin "1") (pinfunction "1_1") (pintype "passive"))
      (node (ref "C10") (pin "1") (pinfunction "1_1") (pintype "passive"))
      (node (ref "C11") (pin "1") (pinfunction "1_1") (pintype "passive"))
      (node (ref "C12") (pin "1") (pinfunction "1_1") (pintype "passive"))
      (node (ref "C13") (pin "1") (pinfunction "1_1") (pintype "passive"))
      (node (ref "C14") (pin "1") (pinfunction "1_1") (pintype "passive"))
      (node (ref "C15") (pin "1") (pinfunction "1_1") (pintype "passive"))
      (node (ref "C16") (pin "1") (pinfunction "1_1") (pintype "passive"))
      (node (ref "C17") (pin "1") (pinfunction "1_1") (pintype "passive"))
      (node (ref "C18") (pin "1") (pinfunction "1_1") (pintype "passive"))
      (node (ref "C19") (pin "1") (pinfunction "1_1") (pintype "passive"))
      (node (ref "C2") (pin "1") (pinfunction "1_1") (pintype "passive"))
      (node (ref "C20") (pin "1") (pinfunction "1_1") (pintype "passive"))
      (node (ref "C21") (pin "1") (pinfunction "1_1") (pintype "passive"))
      (node (ref "C22") (pin "1") (pinfunction "1_1") (pintype "passive"))
      (node (ref "C23") (pin "1") (pinfunction "1_1") (pintype "passive"))
      (node (ref "C24") (pin "1") (pinfunction "1_1") (pintype "passive"))
      (node (ref "C25") (pin "1") (pinfunction "1_1") (pintype "passive"))
      (node (ref "C26") (pin "1") (pinfunction "1_1") (pintype "passive"))
      (node (ref "C27") (pin "1") (pinfunction "1_1") (pintype "passive"))
      (node (ref "C28") (pin "1") (pinfunction "1_1") (pintype "passive"))
      (node (ref "C29") (pin "1") (pinfunction "1_1") (pintype "passive"))
      (node (ref "C3") (pin "1") (pinfunction "1_1") (pintype "passive"))
      (node (ref "C30") (pin "1") (pinfunction "1_1") (pintype "passive"))
      (node (ref "C31") (pin "1") (pinfunction "1_1") (pintype "passive"))
      (node (ref "C32") (pin "1") (pinfunction "1_1") (pintype "passive"))
      (node (ref "C33") (pin "1") (pinfunction "1_1") (pintype "passive"))
      (node (ref "C34") (pin "1") (pinfunction "1_1") (pintype "passive"))
      (node (ref "C35") (pin "1") (pinfunction "1_1") (pintype "passive"))
      (node (ref "C36") (pin "1") (pinfunction "1_1") (pintype "passive"))
      (node (ref "C37") (pin "1") (pinfunction "1_1") (pintype "passive"))
      (node (ref "C38") (pin "1") (pinfunction "1_1") (pintype "passive"))
      (node (ref "C39") (pin "1") (pinfunction "1_1") (pintype "passive"))
      (node (ref "C4") (pin "1") (pinfunction "1_1") (pintype "passive"))
      (node (ref "C40") (pin "1") (pinfunction "1_1") (pintype "passive"))
      (node (ref "C41") (pin "1") (pinfunction "1_1") (pintype "passive"))
      (node (ref "C42") (pin "1") (pinfunction "1_1") (pintype "passive"))
      (node (ref "C43") (pin "1") (pinfunction "1_1") (pintype "passive"))
      (node (ref "C44") (pin "1") (pinfunction "1_1") (pintype "passive"))
      (node (ref "C45") (pin "1") (pinfunction "1_1") (pintype "passive"))
      (node (ref "C46") (pin "1") (pinfunction "1_1") (pintype "passive"))
      (node (ref "C47") (pin "1") (pinfunction "1_1") (pintype "passive"))
      (node (ref "C48") (pin "1") (pinfunction "1_1") (pintype "passive"))
      (node (ref "C49") (pin "1") (pinfunction "1_1") (pintype "passive"))
      (node (ref "C5") (pin "1") (pinfunction "1_1") (pintype "passive"))
      (node (ref "C50") (pin "1") (pinfunction "1_1") (pintype "passive"))
      (node (ref "C6") (pin "1") (pinfunction "1_1") (pintype "passive"))
      (node (ref "C7") (pin "1") (pinfunction "1_1") (pintype "passive"))
      (node (ref "C8") (pin "1") (pinfunction "1_1") (pintype "passive"))
      (node (ref "C9") (pin "1") (pinfunction "1_1") (pintype "passive"))
      (node (ref "R2") (pin "1") (pinfunction "1_1") (pintype "passive"))
      (node (ref "U1") (pin "A10") (pinfunction "VSS_A10") (pintype "passive"))
      (node (ref "U1") (pin "A3") (pinfunction "VSS_A3") (pintype "passive"))
      (node (ref "U1") (pin "AB10") (pinfunction "VSS_AB10") (pintype "passive"))
      (node (ref "U1") (pin "AB3") (pinfunction "VSS_AB3") (pintype "passive"))
      (node (ref "U1") (pin "AB5") (pinfunction "VSS_AB5") (pintype "passive"))
      (node (ref "U1") (pin "AB8") (pinfunction "VSS_AB8") (pintype "passive"))
      (node (ref "U1") (pin "C1") (pinfunction "VSS_C1") (pintype "passive"))
      (node (ref "U1") (pin "C12") (pinfunction "VSS_C12") (pintype "passive"))
      (node (ref "U1") (pin "C5") (pinfunction "VSS_C5") (pintype "passive"))
      (node (ref "U1") (pin "C8") (pinfunction "VSS_C8") (pintype "passive"))
      (node (ref "U1") (pin "D11") (pinfunction "VSS_D11") (pintype "passive"))
      (node (ref "U1") (pin "D2") (pinfunction "VSS_D2") (pintype "passive"))
      (node (ref "U1") (pin "D4") (pinfunction "VSS_D4") (pintype "passive"))
      (node (ref "U1") (pin "D9") (pinfunction "VSS_D9") (pintype "passive"))
      (node (ref "U1") (pin "E1") (pinfunction "VSS_E1") (pintype "passive"))
      (node (ref "U1") (pin "E12") (pinfunction "VSS_E12") (pintype "passive"))
      (node (ref "U1") (pin "E5") (pinfunction "VSS_E5") (pintype "passive"))
      (node (ref "U1") (pin "E8") (pinfunction "VSS_E8") (pintype "passive"))
      (node (ref "U1") (pin "G1") (pinfunction "VSS_G1") (pintype "passive"))
      (node (ref "U1") (pin "G10") (pinfunction "VSS_G10") (pintype "passive"))
      (node (ref "U1") (pin "G12") (pinfunction "VSS_G12") (pintype "passive"))
      (node (ref "U1") (pin "G3") (pinfunction "VSS_G3") (pintype "passive"))
      (node (ref "U1") (pin "G5") (pinfunction "VSS_G5") (pintype "passive"))
      (node (ref "U1") (pin "G8") (pinfunction "VSS_G8") (pintype "passive"))
      (node (ref "U1") (pin "J1") (pinfunction "VSS_J1") (pintype "passive"))
      (node (ref "U1") (pin "J10") (pinfunction "VSS_J10") (pintype "passive"))
      (node (ref "U1") (pin "J12") (pinfunction "VSS_J12") (pintype "passive"))
      (node (ref "U1") (pin "J3") (pinfunction "VSS_J3") (pintype "passive"))
      (node (ref "U1") (pin "K11") (pinfunction "VSS_K11") (pintype "passive"))
      (node (ref "U1") (pin "K2") (pinfunction "VSS_K2") (pintype "passive"))
      (node (ref "U1") (pin "K4") (pinfunction "VSS_K4") (pintype "passive"))
      (node (ref "U1") (pin "K9") (pinfunction "VSS_K9") (pintype "passive"))
      (node (ref "U1") (pin "N11") (pinfunction "VSS_N11") (pintype "passive"))
      (node (ref "U1") (pin "N2") (pinfunction "VSS_N2") (pintype "passive"))
      (node (ref "U1") (pin "N4") (pinfunction "VSS_N4") (pintype "passive"))
      (node (ref "U1") (pin "N9") (pinfunction "VSS_N9") (pintype "passive"))
      (node (ref "U1") (pin "P1") (pinfunction "VSS_P1") (pintype "passive"))
      (node (ref "U1") (pin "P10") (pinfunction "VSS_P10") (pintype "passive"))
      (node (ref "U1") (pin "P12") (pinfunction "VSS_P12") (pintype "passive"))
      (node (ref "U1") (pin "P3") (pinfunction "VSS_P3") (pintype "passive"))
      (node (ref "U1") (pin "T1") (pinfunction "VSS_T1") (pintype "passive"))
      (node (ref "U1") (pin "T10") (pinfunction "VSS_T10") (pintype "passive"))
      (node (ref "U1") (pin "T12") (pinfunction "VSS_T12") (pintype "passive"))
      (node (ref "U1") (pin "T3") (pinfunction "VSS_T3") (pintype "passive"))
      (node (ref "U1") (pin "T5") (pinfunction "VSS_T5") (pintype "passive"))
      (node (ref "U1") (pin "T8") (pinfunction "VSS_T8") (pintype "passive"))
      (node (ref "U1") (pin "V1") (pinfunction "VSS_V1") (pintype "passive"))
      (node (ref "U1") (pin "V12") (pinfunction "VSS_V12") (pintype "passive"))
      (node (ref "U1") (pin "V5") (pinfunction "VSS_V5") (pintype "passive"))
      (node (ref "U1") (pin "V8") (pinfunction "VSS_V8") (pintype "passive"))
      (node (ref "U1") (pin "W11") (pinfunction "VSS_W11") (pintype "passive"))
      (node (ref "U1") (pin "W2") (pinfunction "VSS_W2") (pintype "passive"))
      (node (ref "U1") (pin "W4") (pinfunction "VSS_W4") (pintype "passive"))
      (node (ref "U1") (pin "W9") (pinfunction "VSS_W9") (pintype "passive"))
      (node (ref "U1") (pin "Y1") (pinfunction "VSS_Y1") (pintype "passive"))
      (node (ref "U1") (pin "Y12") (pinfunction "VSS_Y12") (pintype "passive"))
      (node (ref "U1") (pin "Y5") (pinfunction "VSS_Y5") (pintype "passive"))
      (node (ref "U1") (pin "Y8") (pinfunction "VSS_Y8") (pintype "passive"))
    )
    (net (code "65") (name "Net-(U1A-ODT_CA_A)") (class "Default")
      (node (ref "R1") (pin "1") (pinfunction "1_1") (pintype "passive"))
      (node (ref "U1") (pin "G2") (pinfunction "ODT_CA_A_G2") (pintype "passive"))
    )
    (net (code "66") (name "Net-(U1A-ODT_CA_B)") (class "Default")
      (node (ref "R2") (pin "2") (pinfunction "2_2") (pintype "passive"))
      (node (ref "U1") (pin "T2") (pinfunction "ODT_CA_B_T2") (pintype "passive"))
    )
    (net (code "67") (name "Net-(U1A-ZQ0)") (class "Default")
      (node (ref "R3") (pin "1") (pinfunction "1_1") (pintype "passive"))
      (node (ref "U1") (pin "A5") (pinfunction "ZQ0_A5") (pintype "passive"))
    )
    (net (code "68") (name "Net-(U1A-ZQ1)") (class "Default")
      (node (ref "R4") (pin "1") (pinfunction "1_1") (pintype "passive"))
      (node (ref "U1") (pin "A8") (pinfunction "ZQ1_A8") (pintype "passive"))
    )
    (net (code "69") (name "VDD1") (class "Default")
      (node (ref "C21") (pin "2") (pinfunction "2_2") (pintype "passive"))
      (node (ref "C22") (pin "2") (pinfunction "2_2") (pintype "passive"))
      (node (ref "C23") (pin "2") (pinfunction "2_2") (pintype "passive"))
      (node (ref "C24") (pin "2") (pinfunction "2_2") (pintype "passive"))
      (node (ref "C25") (pin "2") (pinfunction "2_2") (pintype "passive"))
      (node (ref "C26") (pin "2") (pinfunction "2_2") (pintype "passive"))
      (node (ref "C27") (pin "2") (pinfunction "2_2") (pintype "passive"))
      (node (ref "C28") (pin "2") (pinfunction "2_2") (pintype "passive"))
      (node (ref "C29") (pin "2") (pinfunction "2_2") (pintype "passive"))
      (node (ref "C30") (pin "2") (pinfunction "2_2") (pintype "passive"))
      (node (ref "C31") (pin "2") (pinfunction "2_2") (pintype "passive"))
      (node (ref "C32") (pin "2") (pinfunction "2_2") (pintype "passive"))
      (node (ref "C33") (pin "2") (pinfunction "2_2") (pintype "passive"))
      (node (ref "C34") (pin "2") (pinfunction "2_2") (pintype "passive"))
      (node (ref "C35") (pin "2") (pinfunction "2_2") (pintype "passive"))
      (node (ref "C36") (pin "2") (pinfunction "2_2") (pintype "passive"))
      (node (ref "C37") (pin "2") (pinfunction "2_2") (pintype "passive"))
      (node (ref "C38") (pin "2") (pinfunction "2_2") (pintype "passive"))
      (node (ref "C39") (pin "2") (pinfunction "2_2") (pintype "passive"))
      (node (ref "C40") (pin "2") (pinfunction "2_2") (pintype "passive"))
      (node (ref "U1") (pin "F1") (pinfunction "VDD1_F1") (pintype "passive"))
      (node (ref "U1") (pin "F12") (pinfunction "VDD1_F12") (pintype "passive"))
      (node (ref "U1") (pin "G4") (pinfunction "VDD1_G4") (pintype "passive"))
      (node (ref "U1") (pin "G9") (pinfunction "VDD1_G9") (pintype "passive"))
      (node (ref "U1") (pin "T4") (pinfunction "VDD1_T4") (pintype "passive"))
      (node (ref "U1") (pin "T9") (pinfunction "VDD1_T9") (pintype "passive"))
      (node (ref "U1") (pin "U1") (pinfunction "VDD1_U1") (pintype "passive"))
      (node (ref "U1") (pin "U12") (pinfunction "VDD1_U12") (pintype "passive"))
    )
    (net (code "70") (name "VDD2") (class "Default")
      (node (ref "C41") (pin "2") (pinfunction "2_2") (pintype "passive"))
      (node (ref "C42") (pin "2") (pinfunction "2_2") (pintype "passive"))
      (node (ref "C43") (pin "2") (pinfunction "2_2") (pintype "passive"))
      (node (ref "C44") (pin "2") (pinfunction "2_2") (pintype "passive"))
      (node (ref "C45") (pin "2") (pinfunction "2_2") (pintype "passive"))
      (node (ref "C46") (pin "2") (pinfunction "2_2") (pintype "passive"))
      (node (ref "C47") (pin "2") (pinfunction "2_2") (pintype "passive"))
      (node (ref "C48") (pin "2") (pinfunction "2_2") (pintype "passive"))
      (node (ref "C49") (pin "2") (pinfunction "2_2") (pintype "passive"))
      (node (ref "C50") (pin "2") (pinfunction "2_2") (pintype "passive"))
      (node (ref "U1") (pin "A4") (pinfunction "VDD2_A4") (pintype "passive"))
      (node (ref "U1") (pin "A9") (pinfunction "VDD2_A9") (pintype "passive"))
      (node (ref "U1") (pin "AB4") (pinfunction "VDD2_AB4") (pintype "passive"))
      (node (ref "U1") (pin "AB9") (pinfunction "VDD2_AB9") (pintype "passive"))
      (node (ref "U1") (pin "F5") (pinfunction "VDD2_F5") (pintype "passive"))
      (node (ref "U1") (pin "F8") (pinfunction "VDD2_F8") (pintype "passive"))
      (node (ref "U1") (pin "H1") (pinfunction "VDD2_H1") (pintype "passive"))
      (node (ref "U1") (pin "H12") (pinfunction "VDD2_H12") (pintype "passive"))
      (node (ref "U1") (pin "H5") (pinfunction "VDD2_H5") (pintype "passive"))
      (node (ref "U1") (pin "H8") (pinfunction "VDD2_H8") (pintype "passive"))
      (node (ref "U1") (pin "K1") (pinfunction "VDD2_K1") (pintype "passive"))
      (node (ref "U1") (pin "K10") (pinfunction "VDD2_K10") (pintype "passive"))
      (node (ref "U1") (pin "K12") (pinfunction "VDD2_K12") (pintype "passive"))
      (node (ref "U1") (pin "K3") (pinfunction "VDD2_K3") (pintype "passive"))
      (node (ref "U1") (pin "N1") (pinfunction "VDD2_N1") (pintype "passive"))
      (node (ref "U1") (pin "N10") (pinfunction "VDD2_N10") (pintype "passive"))
      (node (ref "U1") (pin "N12") (pinfunction "VDD2_N12") (pintype "passive"))
      (node (ref "U1") (pin "N3") (pinfunction "VDD2_N3") (pintype "passive"))
      (node (ref "U1") (pin "R1") (pinfunction "VDD2_R1") (pintype "passive"))
      (node (ref "U1") (pin "R12") (pinfunction "VDD2_R12") (pintype "passive"))
      (node (ref "U1") (pin "R5") (pinfunction "VDD2_R5") (pintype "passive"))
      (node (ref "U1") (pin "R8") (pinfunction "VDD2_R8") (pintype "passive"))
      (node (ref "U1") (pin "U5") (pinfunction "VDD2_U5") (pintype "passive"))
      (node (ref "U1") (pin "U8") (pinfunction "VDD2_U8") (pintype "passive"))
    )
    (net (code "71") (name "VDDQ") (class "Default")
      (node (ref "C1") (pin "2") (pinfunction "2_2") (pintype "passive"))
      (node (ref "C10") (pin "2") (pinfunction "2_2") (pintype "passive"))
      (node (ref "C11") (pin "2") (pinfunction "2_2") (pintype "passive"))
      (node (ref "C12") (pin "2") (pinfunction "2_2") (pintype "passive"))
      (node (ref "C13") (pin "2") (pinfunction "2_2") (pintype "passive"))
      (node (ref "C14") (pin "2") (pinfunction "2_2") (pintype "passive"))
      (node (ref "C15") (pin "2") (pinfunction "2_2") (pintype "passive"))
      (node (ref "C16") (pin "2") (pinfunction "2_2") (pintype "passive"))
      (node (ref "C17") (pin "2") (pinfunction "2_2") (pintype "passive"))
      (node (ref "C18") (pin "2") (pinfunction "2_2") (pintype "passive"))
      (node (ref "C19") (pin "2") (pinfunction "2_2") (pintype "passive"))
      (node (ref "C2") (pin "2") (pinfunction "2_2") (pintype "passive"))
      (node (ref "C20") (pin "2") (pinfunction "2_2") (pintype "passive"))
      (node (ref "C3") (pin "2") (pinfunction "2_2") (pintype "passive"))
      (node (ref "C4") (pin "2") (pinfunction "2_2") (pintype "passive"))
      (node (ref "C5") (pin "2") (pinfunction "2_2") (pintype "passive"))
      (node (ref "C6") (pin "2") (pinfunction "2_2") (pintype "passive"))
      (node (ref "C7") (pin "2") (pinfunction "2_2") (pintype "passive"))
      (node (ref "C8") (pin "2") (pinfunction "2_2") (pintype "passive"))
      (node (ref "C9") (pin "2") (pinfunction "2_2") (pintype "passive"))
      (node (ref "R1") (pin "2") (pinfunction "2_2") (pintype "passive"))
      (node (ref "R3") (pin "2") (pinfunction "2_2") (pintype "passive"))
      (node (ref "R4") (pin "2") (pinfunction "2_2") (pintype "passive"))
      (node (ref "U1") (pin "AA10") (pinfunction "VDDQ_AA10") (pintype "passive"))
      (node (ref "U1") (pin "AA3") (pinfunction "VDDQ_AA3") (pintype "passive"))
      (node (ref "U1") (pin "AA5") (pinfunction "VDDQ_AA5") (pintype "passive"))
      (node (ref "U1") (pin "AA8") (pinfunction "VDDQ_AA8") (pintype "passive"))
      (node (ref "U1") (pin "B10") (pinfunction "VDDQ_B10") (pintype "passive"))
      (node (ref "U1") (pin "B3") (pinfunction "VDDQ_B3") (pintype "passive"))
      (node (ref "U1") (pin "B5") (pinfunction "VDDQ_B5") (pintype "passive"))
      (node (ref "U1") (pin "B8") (pinfunction "VDDQ_B8") (pintype "passive"))
      (node (ref "U1") (pin "D1") (pinfunction "VDDQ_D1") (pintype "passive"))
      (node (ref "U1") (pin "D12") (pinfunction "VDDQ_D12") (pintype "passive"))
      (node (ref "U1") (pin "D5") (pinfunction "VDDQ_D5") (pintype "passive"))
      (node (ref "U1") (pin "D8") (pinfunction "VDDQ_D8") (pintype "passive"))
      (node (ref "U1") (pin "F10") (pinfunction "VDDQ_F10") (pintype "passive"))
      (node (ref "U1") (pin "F3") (pinfunction "VDDQ_F3") (pintype "passive"))
      (node (ref "U1") (pin "U10") (pinfunction "VDDQ_U10") (pintype "passive"))
      (node (ref "U1") (pin "U3") (pinfunction "VDDQ_U3") (pintype "passive"))
      (node (ref "U1") (pin "W1") (pinfunction "VDDQ_W1") (pintype "passive"))
      (node (ref "U1") (pin "W12") (pinfunction "VDDQ_W12") (pintype "passive"))
      (node (ref "U1") (pin "W5") (pinfunction "VDDQ_W5") (pintype "passive"))
      (node (ref "U1") (pin "W8") (pinfunction "VDDQ_W8") (pintype "passive"))
    )
    (net (code "72") (name "unconnected-(U1B-DNU1-PadA1)") (class "Default")
      (node (ref "U1") (pin "A1") (pinfunction "DNU1_A1") (pintype "passive+no_connect"))
    )
    (net (code "73") (name "unconnected-(U1B-DNU2-PadA2)") (class "Default")
      (node (ref "U1") (pin "A2") (pinfunction "DNU2_A2") (pintype "passive+no_connect"))
    )
    (net (code "74") (name "unconnected-(U1B-DNU3-PadA11)") (class "Default")
      (node (ref "U1") (pin "A11") (pinfunction "DNU3_A11") (pintype "passive+no_connect"))
    )
    (net (code "75") (name "unconnected-(U1B-DNU4-PadA12)") (class "Default")
      (node (ref "U1") (pin "A12") (pinfunction "DNU4_A12") (pintype "passive+no_connect"))
    )
    (net (code "76") (name "unconnected-(U1B-DNU5-PadB1)") (class "Default")
      (node (ref "U1") (pin "B1") (pinfunction "DNU5_B1") (pintype "passive+no_connect"))
    )
    (net (code "77") (name "unconnected-(U1B-DNU6-PadB12)") (class "Default")
      (node (ref "U1") (pin "B12") (pinfunction "DNU6_B12") (pintype "passive+no_connect"))
    )
    (net (code "78") (name "unconnected-(U1B-DNU7-PadAA1)") (class "Default")
      (node (ref "U1") (pin "AA1") (pinfunction "DNU7_AA1") (pintype "passive+no_connect"))
    )
    (net (code "79") (name "unconnected-(U1B-DNU8-PadAA12)") (class "Default")
      (node (ref "U1") (pin "AA12") (pinfunction "DNU8_AA12") (pintype "passive+no_connect"))
    )
    (net (code "80") (name "unconnected-(U1B-DNU9-PadAB1)") (class "Default")
      (node (ref "U1") (pin "AB1") (pinfunction "DNU9_AB1") (pintype "passive+no_connect"))
    )
    (net (code "81") (name "unconnected-(U1B-DNU10-PadAB2)") (class "Default")
      (node (ref "U1") (pin "AB2") (pinfunction "DNU10_AB2") (pintype "passive+no_connect"))
    )
    (net (code "82") (name "unconnected-(U1B-DNU11-PadAB11)") (class "Default")
      (node (ref "U1") (pin "AB11") (pinfunction "DNU11_AB11") (pintype "passive+no_connect"))
    )
    (net (code "83") (name "unconnected-(U1B-DNU12-PadAB12)") (class "Default")
      (node (ref "U1") (pin "AB12") (pinfunction "DNU12_AB12") (pintype "passive+no_connect"))
    )
    (net (code "84") (name "unconnected-(U1B-DNU13-PadK8)") (class "Default")
      (node (ref "U1") (pin "K8") (pinfunction "DNU13_K8") (pintype "passive+no_connect"))
    )
    (net (code "85") (name "unconnected-(U1B-DNU14-PadN5)") (class "Default")
      (node (ref "U1") (pin "N5") (pinfunction "DNU14_N5") (pintype "passive+no_connect"))
    )
    (net (code "86") (name "unconnected-(U1B-DNU15-PadK5)") (class "Default")
      (node (ref "U1") (pin "K5") (pinfunction "DNU15_K5") (pintype "passive+no_connect"))
    )
    (net (code "87") (name "unconnected-(U1B-DNU16-PadG11)") (class "Default")
      (node (ref "U1") (pin "G11") (pinfunction "DNU16_G11") (pintype "passive+no_connect"))
    )
    (net (code "88") (name "unconnected-(U1B-DNU17-PadN8)") (class "Default")
      (node (ref "U1") (pin "N8") (pinfunction "DNU17_N8") (pintype "passive+no_connect"))
    )
  )
)
